# FIT_HDMI_X31-7.net
KiCad netlist of a schematic drawn in Altium Designer
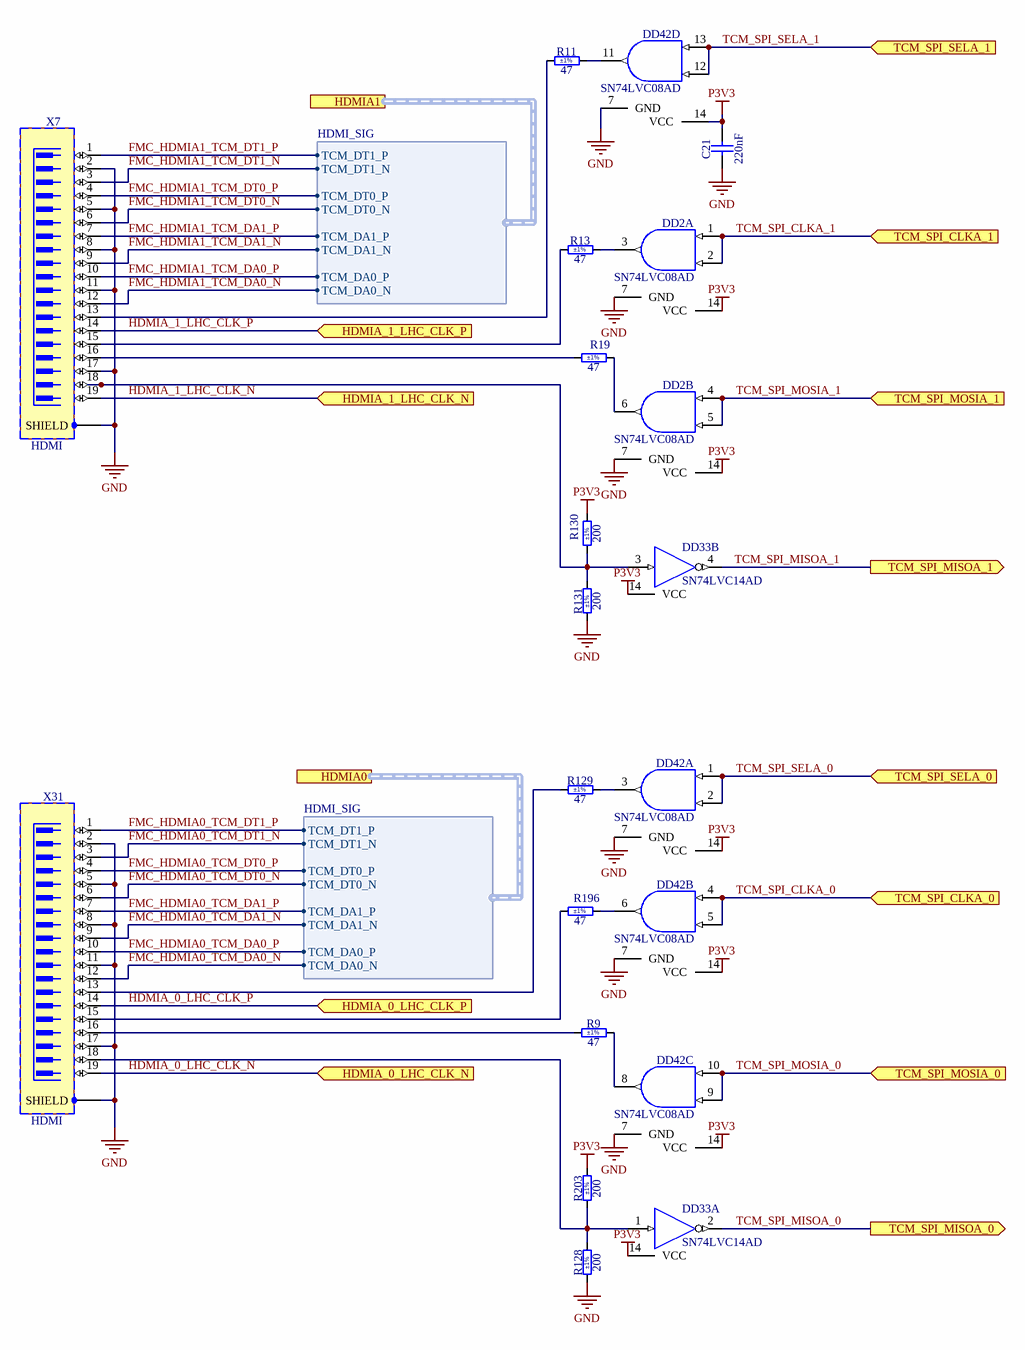
[diagram p0: FIT_HDMI_X31-7.SchDoc]

(export (version "E")
  (design (tool "Eeschema 10.0.6"))
  (components
    (comp (ref "C21")
      (value "220nF")
      (footprint "CAPC2012X135N")
      (description "Non-polarised capacitor")
      (fields
        (field (name "PART NUMBER") "CC0805_220NF_50V_10%_X7R")
        (field (name "VOLTAGE") "50V")
        (field (name "AUTHOR") "CERN DEM JLC")
      )
      (libsource (lib "Capacitors") (part "Capacitor - non polarized"))
    )
    (comp (ref "DD2")
      (value "SN74LVC08AD")
      (footprint "SOIC127P600X175-14N")
      (description "Quad 2-Input AND Gate")
      (fields (field (name "MANUFACTURER") "TEXAS INSTRUMENTS") (field (name "AUTHOR") "CERN DEM JLC"))
      (libsource (lib "ICs And Semiconductors") (part "7408"))
    )
    (comp (ref "DD33")
      (value "SN74LVC14AD")
      (footprint "SOIC127P600X175-14N")
      (description "Hex Schmitt-Trigger Inverter")
      (fields (field (name "MANUFACTURER") "TEXAS INSTRUMENTS") (field (name "AUTHOR") "CERN DEM JMW"))
      (libsource (lib "ICs And Semiconductors") (part "7414"))
    )
    (comp (ref "DD42")
      (value "SN74LVC08AD")
      (footprint "SOIC127P600X175-14N")
      (description "Quad 2-Input AND Gate")
      (fields (field (name "MANUFACTURER") "TEXAS INSTRUMENTS") (field (name "AUTHOR") "CERN DEM JLC"))
      (libsource (lib "ICs And Semiconductors") (part "7408"))
    )
    (comp (ref "R9")
      (value "47")
      (footprint "RESC2012X60N")
      (description "Resistor - 1%")
      (fields
        (field (name "TOLERANCE") "±1%")
        (field (name "PART NUMBER") "R0805_47R_1%_0.125W_100PPM")
        (field (name "POWER") "0.125W")
        (field (name "AUTHOR") "CERN DEM JLC")
      )
      (libsource (lib "Resistors") (part "Resistor - 1%"))
    )
    (comp (ref "R11")
      (value "47")
      (footprint "RESC2012X60N")
      (description "Resistor - 1%")
      (fields
        (field (name "TOLERANCE") "±1%")
        (field (name "PART NUMBER") "R0805_47R_1%_0.125W_100PPM")
        (field (name "POWER") "0.125W")
        (field (name "AUTHOR") "CERN DEM JLC")
      )
      (libsource (lib "Resistors") (part "Resistor - 1%"))
    )
    (comp (ref "R13")
      (value "47")
      (footprint "RESC2012X60N")
      (description "Resistor - 1%")
      (fields
        (field (name "TOLERANCE") "±1%")
        (field (name "PART NUMBER") "R0805_47R_1%_0.125W_100PPM")
        (field (name "POWER") "0.125W")
        (field (name "AUTHOR") "CERN DEM JLC")
      )
      (libsource (lib "Resistors") (part "Resistor - 1%"))
    )
    (comp (ref "R19")
      (value "47")
      (footprint "RESC2012X60N")
      (description "Resistor - 1%")
      (fields
        (field (name "TOLERANCE") "±1%")
        (field (name "PART NUMBER") "R0805_47R_1%_0.125W_100PPM")
        (field (name "POWER") "0.125W")
        (field (name "AUTHOR") "CERN DEM JLC")
      )
      (libsource (lib "Resistors") (part "Resistor - 1%"))
    )
    (comp (ref "R128")
      (value "200")
      (footprint "RESC2012X60N")
      (description "Resistor - 1%")
      (fields
        (field (name "TOLERANCE") "±1%")
        (field (name "PART NUMBER") "R0805_200R_1%_0.125W_100PPM")
        (field (name "POWER") "0.125W")
        (field (name "AUTHOR") "CERN DEM JLC")
      )
      (libsource (lib "Resistors") (part "Resistor - 1%"))
    )
    (comp (ref "R129")
      (value "47")
      (footprint "RESC2012X60N")
      (description "Resistor - 1%")
      (fields
        (field (name "TOLERANCE") "±1%")
        (field (name "PART NUMBER") "R0805_47R_1%_0.125W_100PPM")
        (field (name "POWER") "0.125W")
        (field (name "AUTHOR") "CERN DEM JLC")
      )
      (libsource (lib "Resistors") (part "Resistor - 1%"))
    )
    (comp (ref "R130")
      (value "200")
      (footprint "RESC2012X60N")
      (description "Resistor - 1%")
      (fields
        (field (name "TOLERANCE") "±1%")
        (field (name "PART NUMBER") "R0805_200R_1%_0.125W_100PPM")
        (field (name "POWER") "0.125W")
        (field (name "AUTHOR") "CERN DEM JLC")
      )
      (libsource (lib "Resistors") (part "Resistor - 1%"))
    )
    (comp (ref "R131")
      (value "200")
      (footprint "RESC2012X60N")
      (description "Resistor - 1%")
      (fields
        (field (name "TOLERANCE") "±1%")
        (field (name "PART NUMBER") "R0805_200R_1%_0.125W_100PPM")
        (field (name "POWER") "0.125W")
        (field (name "AUTHOR") "CERN DEM JLC")
      )
      (libsource (lib "Resistors") (part "Resistor - 1%"))
    )
    (comp (ref "R196")
      (value "47")
      (footprint "RESC2012X60N")
      (description "Resistor - 1%")
      (fields
        (field (name "TOLERANCE") "±1%")
        (field (name "PART NUMBER") "R0805_47R_1%_0.125W_100PPM")
        (field (name "POWER") "0.125W")
        (field (name "AUTHOR") "CERN DEM JLC")
      )
      (libsource (lib "Resistors") (part "Resistor - 1%"))
    )
    (comp (ref "R203")
      (value "200")
      (footprint "RESC2012X60N")
      (description "Resistor - 1%")
      (fields
        (field (name "TOLERANCE") "±1%")
        (field (name "PART NUMBER") "R0805_200R_1%_0.125W_100PPM")
        (field (name "POWER") "0.125W")
        (field (name "AUTHOR") "CERN DEM JLC")
      )
      (libsource (lib "Resistors") (part "Resistor - 1%"))
    )
    (comp (ref "X7")
      (value "HDMI")
      (footprint "TYCO_2007435-1")
      (description "Connector HDMI 19 Male + 1 Shield")
      (fields
        (field (name "PART NUMBER") "TYCO_2007435-1")
        (field (name "MANUFACTURER") "TYCO ELECTRONICS")
        (field (name "AUTHOR") "CERN DEM MR")
      )
      (libsource (lib "Connectors") (part "Connector HDMI 19 Male + 1 Shield"))
    )
    (comp (ref "X31")
      (value "HDMI")
      (footprint "TYCO_2007435-1")
      (description "Connector HDMI 19 Male + 1 Shield")
      (fields
        (field (name "PART NUMBER") "TYCO_2007435-1")
        (field (name "MANUFACTURER") "TYCO ELECTRONICS")
        (field (name "AUTHOR") "CERN DEM MR")
      )
      (libsource (lib "Connectors") (part "Connector HDMI 19 Male + 1 Shield"))
    )
  )
  (nets
    (net (code "2") (name "/FMC_HDMIA0_TCM_DA0_N") (class "Default")
      (node (ref "X31") (pin "12") (pinfunction "12_12") (pintype "bidirectional"))
    )
    (net (code "3") (name "/FMC_HDMIA0_TCM_DA0_P") (class "Default")
      (node (ref "X31") (pin "10") (pinfunction "10_10") (pintype "bidirectional"))
    )
    (net (code "4") (name "/FMC_HDMIA0_TCM_DA1_N") (class "Default")
      (node (ref "X31") (pin "9") (pinfunction "9_9") (pintype "bidirectional"))
    )
    (net (code "5") (name "/FMC_HDMIA0_TCM_DA1_P") (class "Default")
      (node (ref "X31") (pin "7") (pinfunction "7_7") (pintype "bidirectional"))
    )
    (net (code "6") (name "/FMC_HDMIA0_TCM_DT0_N") (class "Default")
      (node (ref "X31") (pin "6") (pinfunction "6_6") (pintype "bidirectional"))
    )
    (net (code "7") (name "/FMC_HDMIA0_TCM_DT0_P") (class "Default")
      (node (ref "X31") (pin "4") (pinfunction "4_4") (pintype "bidirectional"))
    )
    (net (code "8") (name "/FMC_HDMIA0_TCM_DT1_N") (class "Default")
      (node (ref "X31") (pin "3") (pinfunction "3_3") (pintype "bidirectional"))
    )
    (net (code "9") (name "/FMC_HDMIA0_TCM_DT1_P") (class "Default")
      (node (ref "X31") (pin "1") (pinfunction "1_1") (pintype "bidirectional"))
    )
    (net (code "10") (name "/FMC_HDMIA1_TCM_DA0_N") (class "Default")
      (node (ref "X7") (pin "12") (pinfunction "12_12") (pintype "bidirectional"))
    )
    (net (code "11") (name "/FMC_HDMIA1_TCM_DA0_P") (class "Default")
      (node (ref "X7") (pin "10") (pinfunction "10_10") (pintype "bidirectional"))
    )
    (net (code "12") (name "/FMC_HDMIA1_TCM_DA1_N") (class "Default")
      (node (ref "X7") (pin "9") (pinfunction "9_9") (pintype "bidirectional"))
    )
    (net (code "13") (name "/FMC_HDMIA1_TCM_DA1_P") (class "Default")
      (node (ref "X7") (pin "7") (pinfunction "7_7") (pintype "bidirectional"))
    )
    (net (code "14") (name "/FMC_HDMIA1_TCM_DT0_N") (class "Default")
      (node (ref "X7") (pin "6") (pinfunction "6_6") (pintype "bidirectional"))
    )
    (net (code "15") (name "/FMC_HDMIA1_TCM_DT0_P") (class "Default")
      (node (ref "X7") (pin "4") (pinfunction "4_4") (pintype "bidirectional"))
    )
    (net (code "16") (name "/FMC_HDMIA1_TCM_DT1_N") (class "Default")
      (node (ref "X7") (pin "3") (pinfunction "3_3") (pintype "bidirectional"))
    )
    (net (code "17") (name "/FMC_HDMIA1_TCM_DT1_P") (class "Default")
      (node (ref "X7") (pin "1") (pinfunction "1_1") (pintype "bidirectional"))
    )
    (net (code "18") (name "/HDMIA_0_LHC_CLK_N") (class "Default")
      (node (ref "X31") (pin "19") (pinfunction "19_19") (pintype "bidirectional"))
    )
    (net (code "19") (name "/HDMIA_0_LHC_CLK_P") (class "Default")
      (node (ref "X31") (pin "14") (pinfunction "14_14") (pintype "bidirectional"))
    )
    (net (code "20") (name "/HDMIA_1_LHC_CLK_N") (class "Default")
      (node (ref "X7") (pin "19") (pinfunction "19_19") (pintype "bidirectional"))
    )
    (net (code "21") (name "/HDMIA_1_LHC_CLK_P") (class "Default")
      (node (ref "X7") (pin "14") (pinfunction "14_14") (pintype "bidirectional"))
    )
    (net (code "22") (name "/TCM_SPI_CLKA_0") (class "Default")
      (node (ref "DD42") (pin "4") (pinfunction "A_4") (pintype "input"))
      (node (ref "DD42") (pin "5") (pinfunction "B_5") (pintype "input"))
    )
    (net (code "23") (name "/TCM_SPI_CLKA_1") (class "Default")
      (node (ref "DD2") (pin "1") (pinfunction "A_1") (pintype "input"))
      (node (ref "DD2") (pin "2") (pinfunction "B_2") (pintype "input"))
    )
    (net (code "24") (name "/TCM_SPI_MISOA_0") (class "Default")
      (node (ref "DD33") (pin "2") (pinfunction "OUT_2") (pintype "output"))
    )
    (net (code "25") (name "/TCM_SPI_MISOA_1") (class "Default")
      (node (ref "DD33") (pin "4") (pinfunction "OUT_4") (pintype "output"))
    )
    (net (code "26") (name "/TCM_SPI_MOSIA_0") (class "Default")
      (node (ref "DD42") (pin "10") (pinfunction "A_10") (pintype "input"))
      (node (ref "DD42") (pin "9") (pinfunction "B_9") (pintype "input"))
    )
    (net (code "27") (name "/TCM_SPI_MOSIA_1") (class "Default")
      (node (ref "DD2") (pin "4") (pinfunction "A_4") (pintype "input"))
      (node (ref "DD2") (pin "5") (pinfunction "B_5") (pintype "input"))
    )
    (net (code "28") (name "/TCM_SPI_SELA_0") (class "Default")
      (node (ref "DD42") (pin "1") (pinfunction "A_1") (pintype "input"))
      (node (ref "DD42") (pin "2") (pinfunction "B_2") (pintype "input"))
    )
    (net (code "29") (name "/TCM_SPI_SELA_1") (class "Default")
      (node (ref "DD42") (pin "12") (pinfunction "B_12") (pintype "input"))
      (node (ref "DD42") (pin "13") (pinfunction "A_13") (pintype "input"))
    )
    (net (code "31") (name "GND") (class "Default")
      (node (ref "C21") (pin "1") (pinfunction "1_1") (pintype "passive"))
      (node (ref "DD2") (pin "7") (pinfunction "GND_7") (pintype "power_in"))
      (node (ref "DD33") (pin "7") (pinfunction "GND_7") (pintype "power_in"))
      (node (ref "DD42") (pin "7") (pinfunction "GND_7") (pintype "power_in"))
      (node (ref "R128") (pin "1") (pinfunction "1_1") (pintype "passive"))
      (node (ref "R131") (pin "1") (pinfunction "1_1") (pintype "passive"))
      (node (ref "X31") (pin "11") (pinfunction "11_11") (pintype "bidirectional"))
      (node (ref "X31") (pin "17") (pinfunction "17_17") (pintype "bidirectional"))
      (node (ref "X31") (pin "2") (pinfunction "2_2") (pintype "bidirectional"))
      (node (ref "X31") (pin "5") (pinfunction "5_5") (pintype "bidirectional"))
      (node (ref "X31") (pin "8") (pinfunction "8_8") (pintype "bidirectional"))
      (node (ref "X31") (pin "SHIELD") (pinfunction "SHIELD_SHIELD") (pintype "power_in"))
      (node (ref "X7") (pin "11") (pinfunction "11_11") (pintype "bidirectional"))
      (node (ref "X7") (pin "17") (pinfunction "17_17") (pintype "bidirectional"))
      (node (ref "X7") (pin "2") (pinfunction "2_2") (pintype "bidirectional"))
      (node (ref "X7") (pin "5") (pinfunction "5_5") (pintype "bidirectional"))
      (node (ref "X7") (pin "8") (pinfunction "8_8") (pintype "bidirectional"))
      (node (ref "X7") (pin "SHIELD") (pinfunction "SHIELD_SHIELD") (pintype "power_in"))
    )
    (net (code "32") (name "Net-(DD2A-Y)") (class "Default")
      (node (ref "DD2") (pin "3") (pinfunction "Y_3") (pintype "output"))
      (node (ref "R13") (pin "2") (pinfunction "2_2") (pintype "passive"))
    )
    (net (code "33") (name "Net-(DD2B-Y)") (class "Default")
      (node (ref "DD2") (pin "6") (pinfunction "Y_6") (pintype "output"))
      (node (ref "R19") (pin "2") (pinfunction "2_2") (pintype "passive"))
    )
    (net (code "34") (name "Net-(DD33A-IN)") (class "Default")
      (node (ref "DD33") (pin "1") (pinfunction "IN_1") (pintype "input"))
      (node (ref "R128") (pin "2") (pinfunction "2_2") (pintype "passive"))
      (node (ref "R203") (pin "1") (pinfunction "1_1") (pintype "passive"))
      (node (ref "X31") (pin "18") (pinfunction "18_18") (pintype "bidirectional"))
    )
    (net (code "35") (name "Net-(DD33B-IN)") (class "Default")
      (node (ref "DD33") (pin "3") (pinfunction "IN_3") (pintype "input"))
      (node (ref "R130") (pin "1") (pinfunction "1_1") (pintype "passive"))
      (node (ref "R131") (pin "2") (pinfunction "2_2") (pintype "passive"))
      (node (ref "X7") (pin "18") (pinfunction "18_18") (pintype "bidirectional"))
    )
    (net (code "36") (name "Net-(DD42A-Y)") (class "Default")
      (node (ref "DD42") (pin "3") (pinfunction "Y_3") (pintype "output"))
      (node (ref "R129") (pin "2") (pinfunction "2_2") (pintype "passive"))
    )
    (net (code "37") (name "Net-(DD42B-Y)") (class "Default")
      (node (ref "DD42") (pin "6") (pinfunction "Y_6") (pintype "output"))
      (node (ref "R196") (pin "2") (pinfunction "2_2") (pintype "passive"))
    )
    (net (code "38") (name "Net-(DD42C-Y)") (class "Default")
      (node (ref "DD42") (pin "8") (pinfunction "Y_8") (pintype "output"))
      (node (ref "R9") (pin "2") (pinfunction "2_2") (pintype "passive"))
    )
    (net (code "39") (name "Net-(DD42D-Y)") (class "Default")
      (node (ref "DD42") (pin "11") (pinfunction "Y_11") (pintype "output"))
      (node (ref "R11") (pin "2") (pinfunction "2_2") (pintype "passive"))
    )
    (net (code "40") (name "Net-(R9-Pad1)") (class "Default")
      (node (ref "R9") (pin "1") (pinfunction "1_1") (pintype "passive"))
      (node (ref "X31") (pin "16") (pinfunction "16_16") (pintype "bidirectional"))
    )
    (net (code "41") (name "Net-(R11-Pad1)") (class "Default")
      (node (ref "R11") (pin "1") (pinfunction "1_1") (pintype "passive"))
      (node (ref "X7") (pin "13") (pinfunction "13_13") (pintype "bidirectional"))
    )
    (net (code "42") (name "Net-(R13-Pad1)") (class "Default")
      (node (ref "R13") (pin "1") (pinfunction "1_1") (pintype "passive"))
      (node (ref "X7") (pin "15") (pinfunction "15_15") (pintype "bidirectional"))
    )
    (net (code "43") (name "Net-(R19-Pad1)") (class "Default")
      (node (ref "R19") (pin "1") (pinfunction "1_1") (pintype "passive"))
      (node (ref "X7") (pin "16") (pinfunction "16_16") (pintype "bidirectional"))
    )
    (net (code "44") (name "Net-(R129-Pad1)") (class "Default")
      (node (ref "R129") (pin "1") (pinfunction "1_1") (pintype "passive"))
      (node (ref "X31") (pin "13") (pinfunction "13_13") (pintype "bidirectional"))
    )
    (net (code "45") (name "Net-(R196-Pad1)") (class "Default")
      (node (ref "R196") (pin "1") (pinfunction "1_1") (pintype "passive"))
      (node (ref "X31") (pin "15") (pinfunction "15_15") (pintype "bidirectional"))
    )
    (net (code "46") (name "P3V3") (class "Default")
      (node (ref "C21") (pin "2") (pinfunction "2_2") (pintype "passive"))
      (node (ref "DD2") (pin "14") (pinfunction "VCC_14") (pintype "power_in"))
      (node (ref "DD33") (pin "14") (pinfunction "VCC_14") (pintype "power_in"))
      (node (ref "DD42") (pin "14") (pinfunction "VCC_14") (pintype "power_in"))
      (node (ref "R130") (pin "2") (pinfunction "2_2") (pintype "passive"))
      (node (ref "R203") (pin "2") (pinfunction "2_2") (pintype "passive"))
    )
  )
)
